# quadcopter.net
KiCad netlist of a schematic drawn in EAGLE
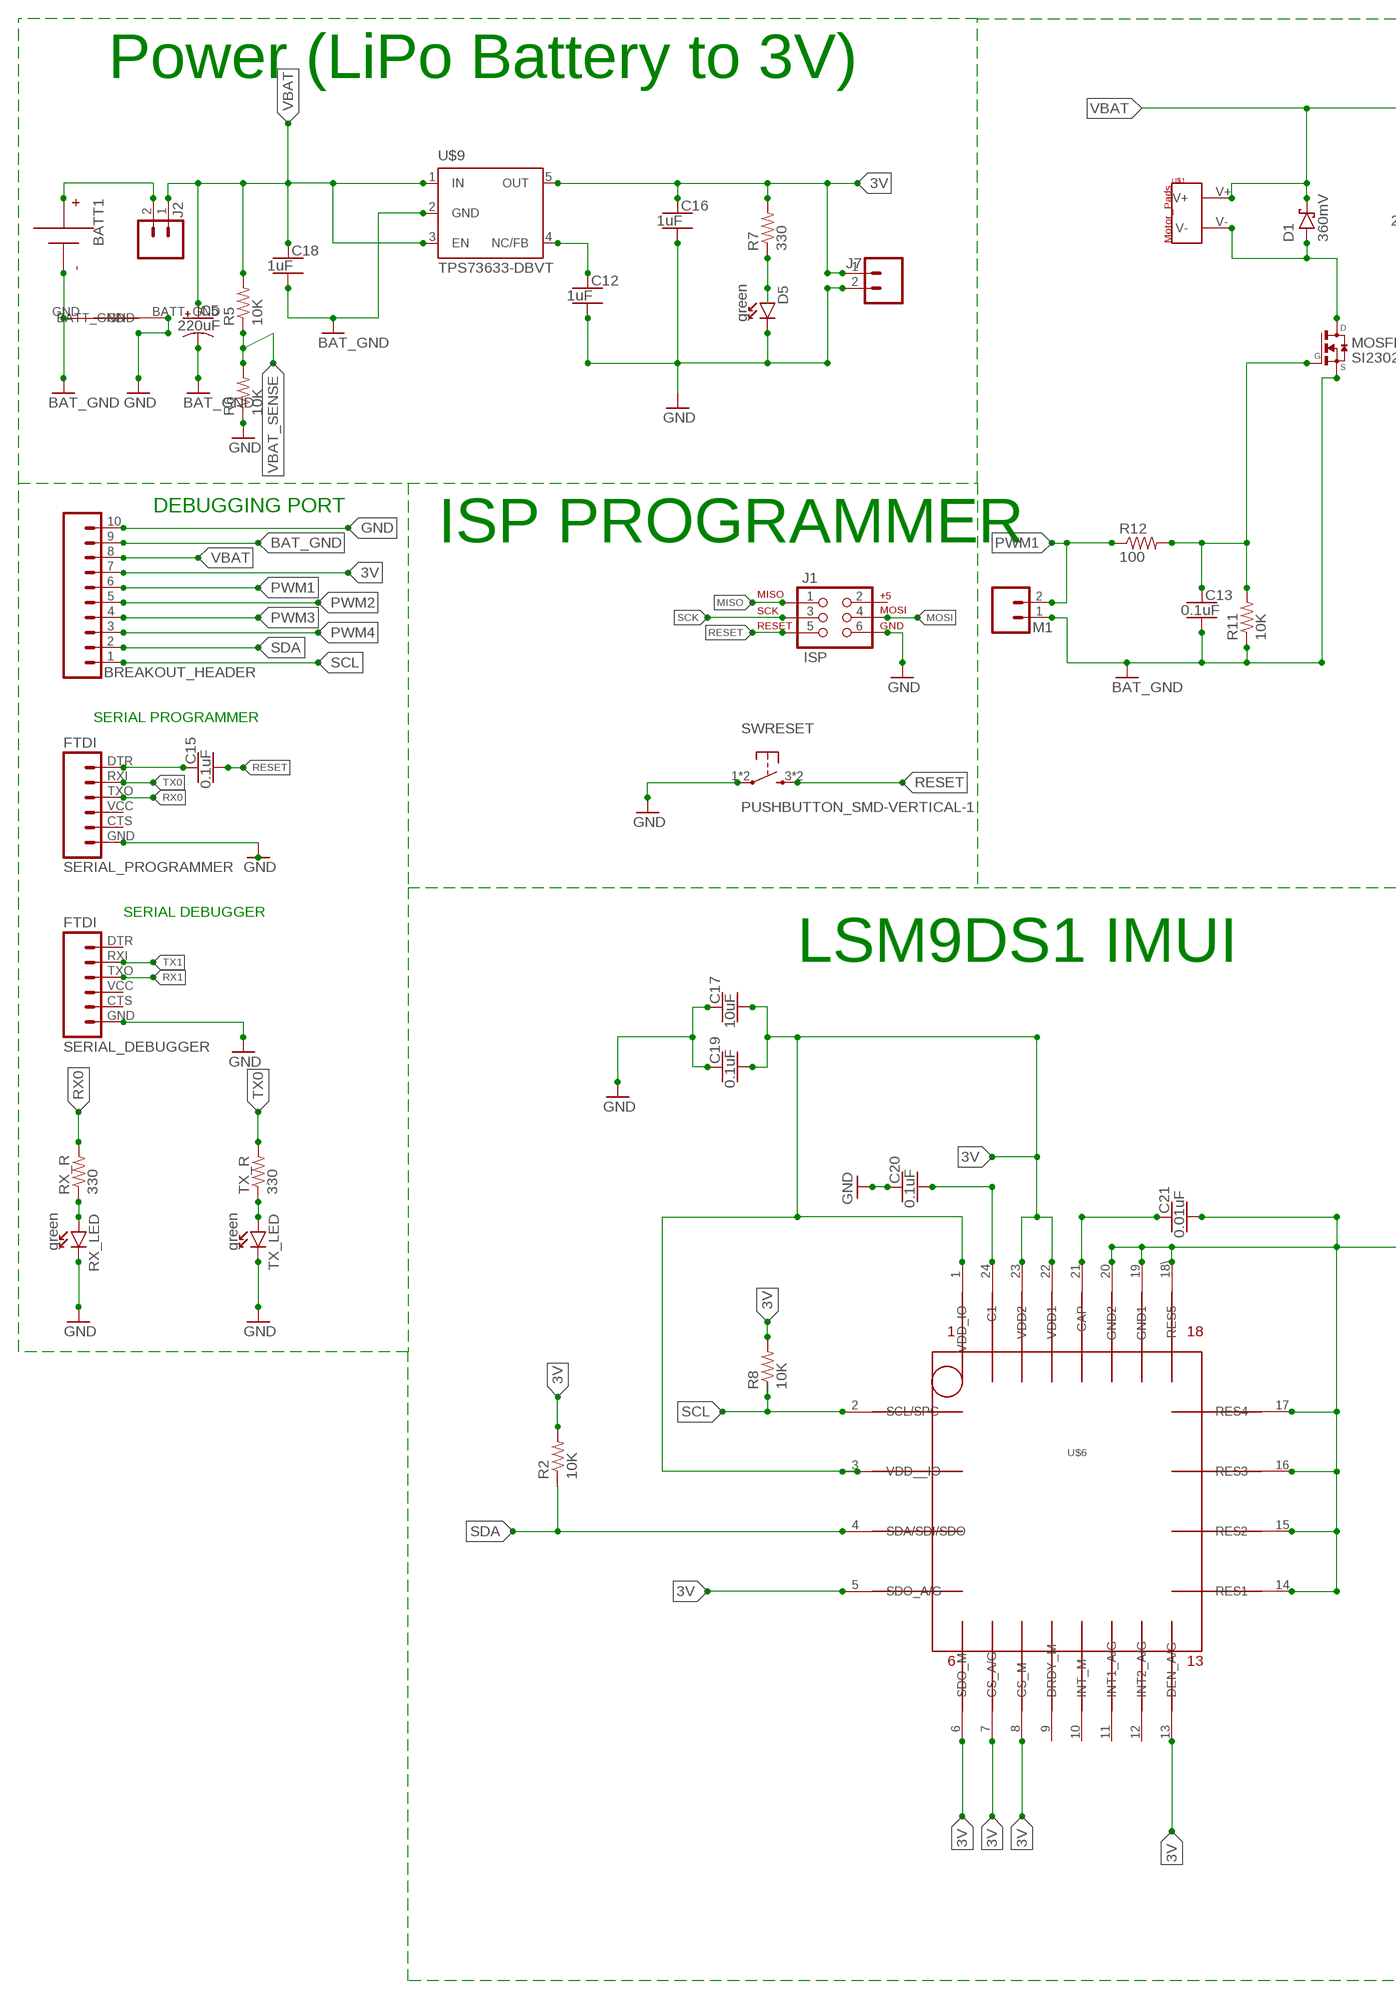
[diagram p0: schematic, sheet 1, part 1 of 2]
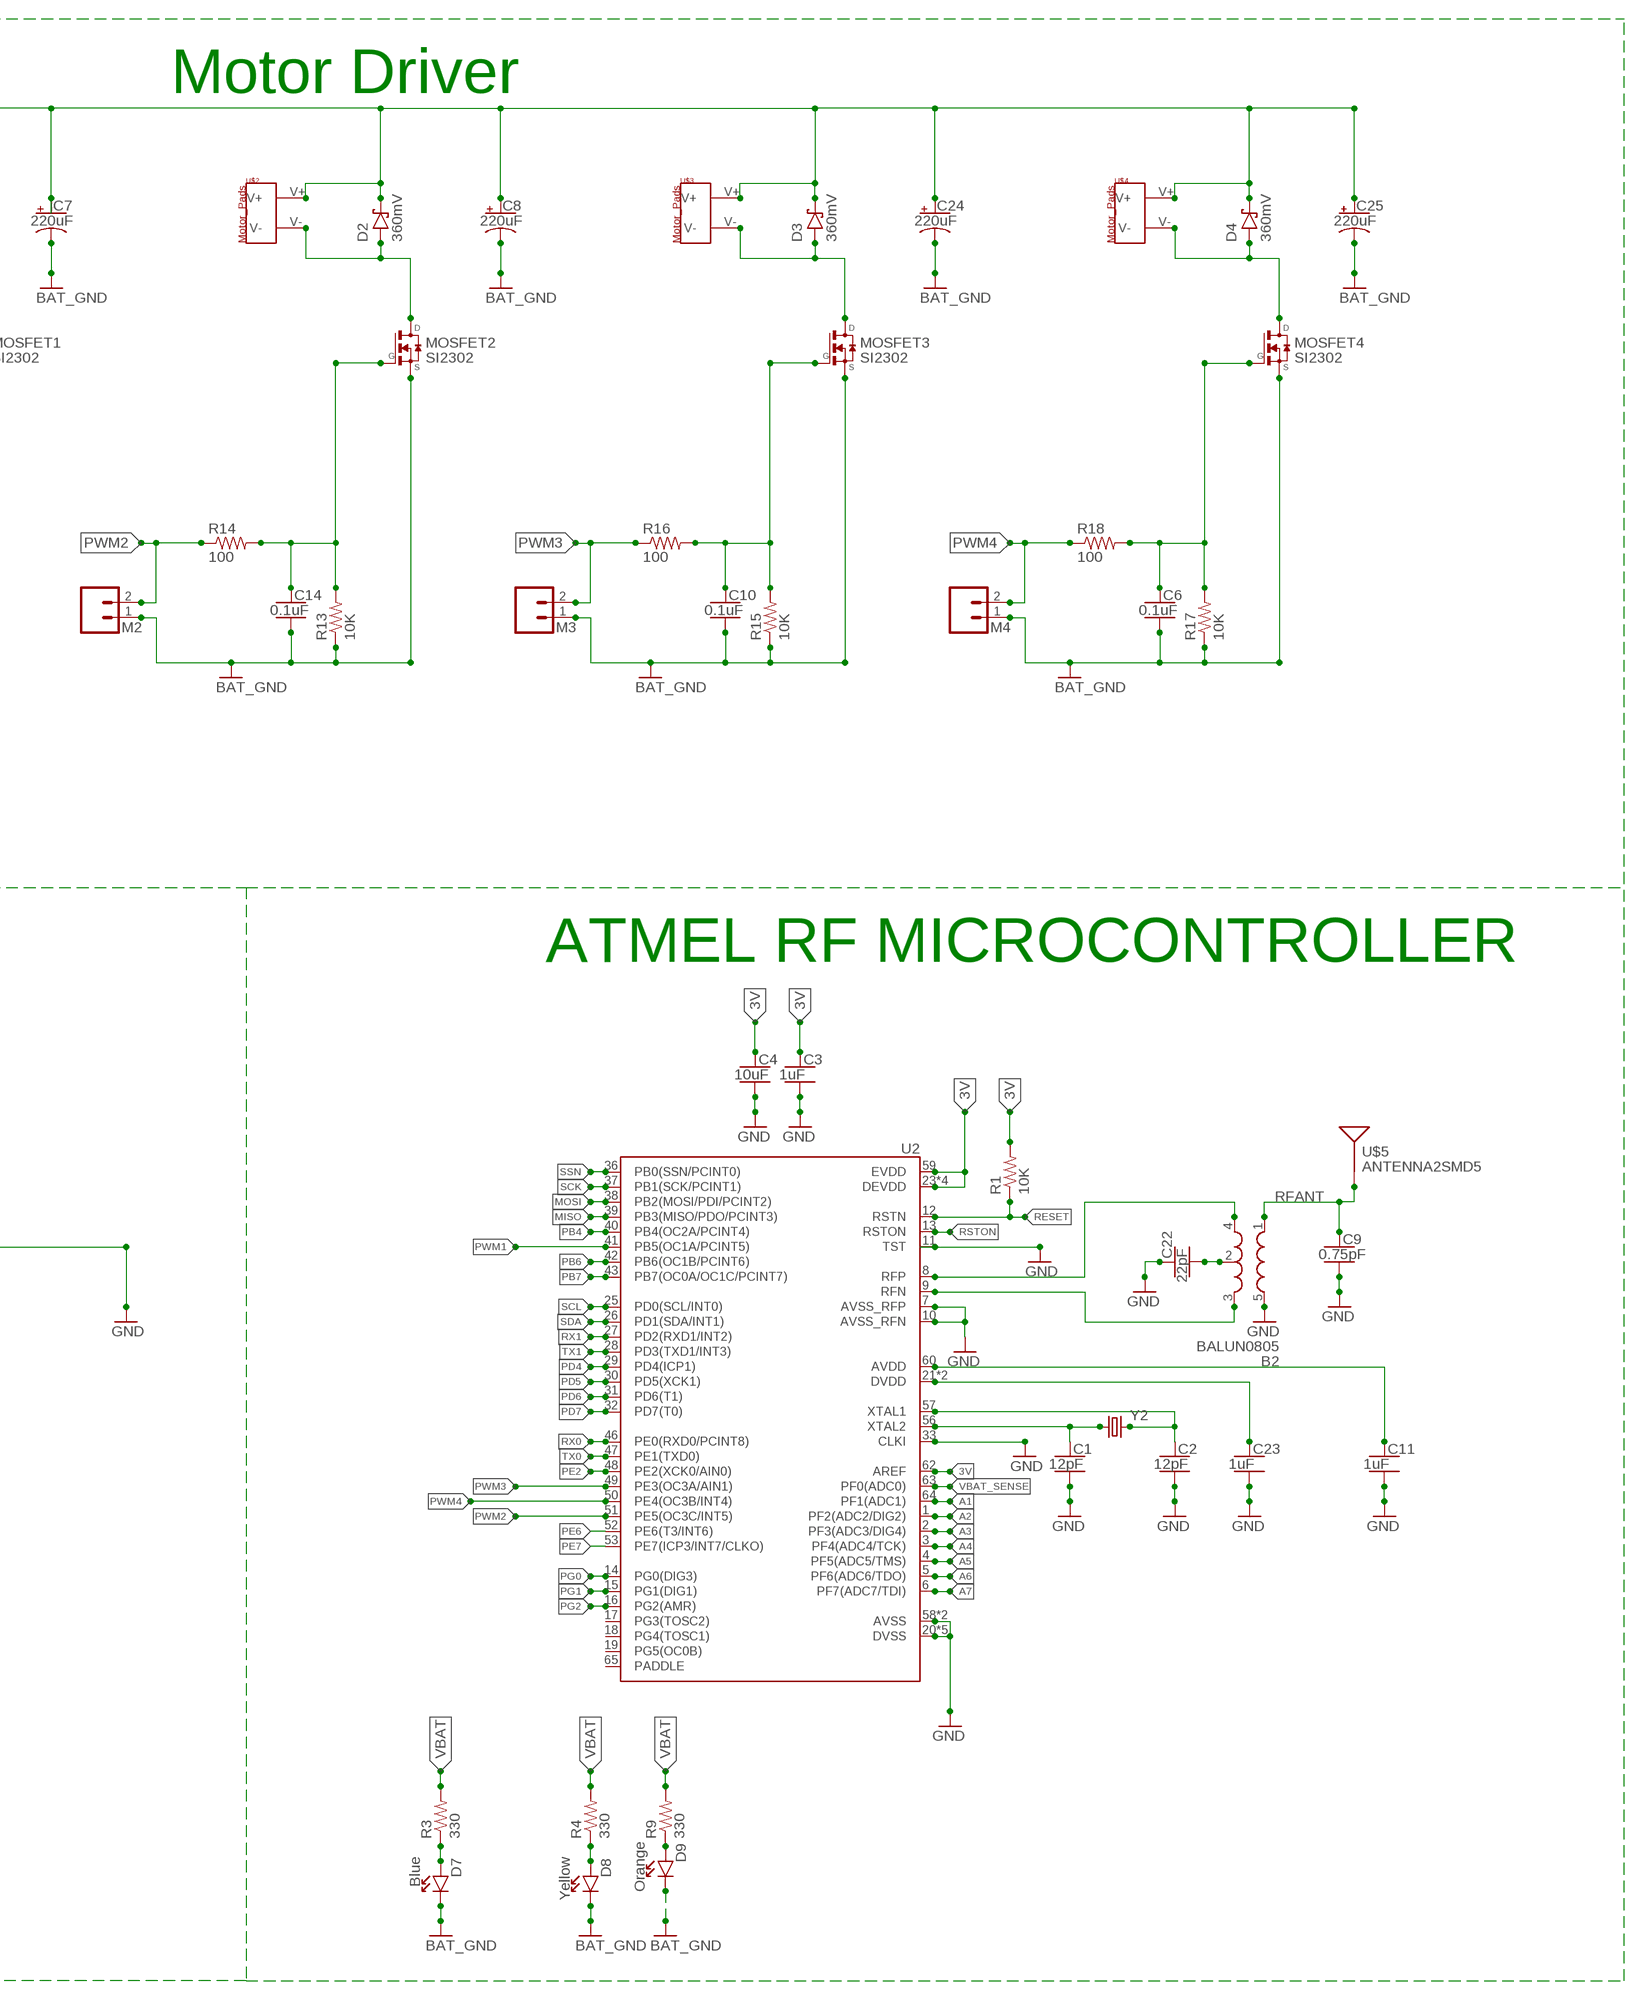
[diagram p1: schematic, sheet 1, part 2 of 2]

(export (version "E")
  (design (tool "Eeschema 10.0.6"))
  (components
    (comp (ref "B2")
      (value "BALUN0805")
      (footprint "eagle-import:BALUN")
      (fields (field (name "MFR") "Wurth Electronics Inc") (field (name "MPN") "748421245"))
      (libsource (lib "eagle-import") (part "BALUN0805"))
    )
    (comp (ref "BATT1")
      (value "BATTERY-HUBSAN-W/HOLDER")
      (footprint "eagle-import:BATTERY-W_HOLDER-380MAH-HUBSAN")
      (fields
        (field (name "MFR") "HUBSAN")
        (field (name "MPN") "X4-H107C-8-in-1")
        (field (name "CREATOR") "Swanson")
      )
      (libsource (lib "eagle-import") (part "BATTERY-HUBSAN-W/HOLDER"))
    )
    (comp (ref "BREAKOUT_HEADER")
      (value "SIP-10_TH-254X10")
      (footprint "eagle-import:HDRV10W63P254_10X1_2540X254H838_HS")
      (fields (field (name "MFR") "Amphenol FCI") (field (name "MPN") "68000-110HLF"))
      (libsource (lib "eagle-import") (part "SIP-10_TH-254X10"))
    )
    (comp (ref "C1")
      (value "12pF")
      (footprint "eagle-import:CAPC2012X140_HS")
      (fields
        (field (name "MFR") "Murata Electronics North America")
        (field (name "MPN") "GRM21A5C2E120JW01D")
      )
      (libsource (lib "eagle-import") (part "CAPACITOR-NP_SMD-2012-0805_CERAMIC-12PF"))
    )
    (comp (ref "C2")
      (value "12pF")
      (footprint "eagle-import:CAPC2012X140_HS")
      (fields
        (field (name "MFR") "Murata Electronics North America")
        (field (name "MPN") "GRM21A5C2E120JW01D")
      )
      (libsource (lib "eagle-import") (part "CAPACITOR-NP_SMD-2012-0805_CERAMIC-12PF"))
    )
    (comp (ref "C3")
      (value "1uF")
      (footprint "eagle-import:CAPC2012X140_HS")
      (fields
        (field (name "MFR") "Murata Electronics North America")
        (field (name "MPN") "GRM21BR71H105KA12L")
      )
      (libsource (lib "eagle-import") (part "CAPACITOR-NP_SMD-2012-0805_CERAMIC-1UF"))
    )
    (comp (ref "C4")
      (value "10uF")
      (footprint "eagle-import:CAPC2012X140_HS")
      (fields
        (field (name "MFR") "Murata Electronics North America")
        (field (name "MPN") "GRM21BR61E106KA73L")
      )
      (libsource (lib "eagle-import") (part "CAPACITOR-NP_SMD-2012-0805_CERAMIC-10UF"))
    )
    (comp (ref "C5")
      (value "220uF")
      (footprint "eagle-import:CAPMP7343X310_HS")
      (fields (field (name "MFR") "AVX Corporation") (field (name "MPN") "TAJD227K006RNJ"))
      (libsource (lib "eagle-import") (part "CAPACITOR-POL_SMD-7043-D_TANTALUM-220UF"))
    )
    (comp (ref "C6")
      (value "0.1uF")
      (footprint "eagle-import:CAPC2012X140_HS")
      (fields
        (field (name "MFR") "Murata Electronics North America")
        (field (name "MPN") "GRM21BR71H104KA01L")
      )
      (libsource (lib "eagle-import") (part "CAPACITOR-NP_SMD-2012-0805_CERAMIC-0.1UF"))
    )
    (comp (ref "C7")
      (value "220uF")
      (footprint "eagle-import:CAPMP7343X310_HS")
      (fields (field (name "MFR") "AVX Corporation") (field (name "MPN") "TAJD227K006RNJ"))
      (libsource (lib "eagle-import") (part "CAPACITOR-POL_SMD-7043-D_TANTALUM-220UF"))
    )
    (comp (ref "C8")
      (value "220uF")
      (footprint "eagle-import:CAPMP7343X310_HS")
      (fields (field (name "MFR") "AVX Corporation") (field (name "MPN") "TAJD227K006RNJ"))
      (libsource (lib "eagle-import") (part "CAPACITOR-POL_SMD-7043-D_TANTALUM-220UF"))
    )
    (comp (ref "C9")
      (value "0.75pF")
      (footprint "eagle-import:CAPC2012X140_HS")
      (fields
        (field (name "MFR") "Murata Electronics North America")
        (field (name "MPN") "GQM2195C2AR75CB01D")
      )
      (libsource (lib "eagle-import") (part "CAPACITOR-NP_SMD-2012-0805_CERAMIC-0.75PF"))
    )
    (comp (ref "C10")
      (value "0.1uF")
      (footprint "eagle-import:CAPC2012X140_HS")
      (fields
        (field (name "MFR") "Murata Electronics North America")
        (field (name "MPN") "GRM21BR71H104KA01L")
      )
      (libsource (lib "eagle-import") (part "CAPACITOR-NP_SMD-2012-0805_CERAMIC-0.1UF"))
    )
    (comp (ref "C11")
      (value "1uF")
      (footprint "eagle-import:CAPC2012X140_HS")
      (fields
        (field (name "MFR") "Murata Electronics North America")
        (field (name "MPN") "GRM21BR71H105KA12L")
      )
      (libsource (lib "eagle-import") (part "CAPACITOR-NP_SMD-2012-0805_CERAMIC-1UF"))
    )
    (comp (ref "C12")
      (value "1uF")
      (footprint "eagle-import:CAPC2012X140_HS")
      (fields
        (field (name "MFR") "Murata Electronics North America")
        (field (name "MPN") "GRM21BR71H105KA12L")
      )
      (libsource (lib "eagle-import") (part "CAPACITOR-NP_SMD-2012-0805_CERAMIC-1UF"))
    )
    (comp (ref "C13")
      (value "0.1uF")
      (footprint "eagle-import:CAPC2012X140_HS")
      (fields
        (field (name "MFR") "Murata Electronics North America")
        (field (name "MPN") "GRM21BR71H104KA01L")
      )
      (libsource (lib "eagle-import") (part "CAPACITOR-NP_SMD-2012-0805_CERAMIC-0.1UF"))
    )
    (comp (ref "C14")
      (value "0.1uF")
      (footprint "eagle-import:CAPC2012X140_HS")
      (fields
        (field (name "MFR") "Murata Electronics North America")
        (field (name "MPN") "GRM21BR71H104KA01L")
      )
      (libsource (lib "eagle-import") (part "CAPACITOR-NP_SMD-2012-0805_CERAMIC-0.1UF"))
    )
    (comp (ref "C15")
      (value "0.1uF")
      (footprint "eagle-import:CAPC2012X140_HS")
      (fields
        (field (name "MFR") "Murata Electronics North America")
        (field (name "MPN") "GRM21BR71H104KA01L")
      )
      (libsource (lib "eagle-import") (part "CAPACITOR-NP_SMD-2012-0805_CERAMIC-0.1UF"))
    )
    (comp (ref "C16")
      (value "1uF")
      (footprint "eagle-import:CAPC2012X140_HS")
      (fields
        (field (name "MFR") "Murata Electronics North America")
        (field (name "MPN") "GRM21BR71H105KA12L")
      )
      (libsource (lib "eagle-import") (part "CAPACITOR-NP_SMD-2012-0805_CERAMIC-1UF"))
    )
    (comp (ref "C17")
      (value "10uF")
      (footprint "eagle-import:CAPC2012X140_HS")
      (fields
        (field (name "MFR") "Murata Electronics North America")
        (field (name "MPN") "GRM21BR61E106KA73L")
      )
      (libsource (lib "eagle-import") (part "CAPACITOR-NP_SMD-2012-0805_CERAMIC-10UF"))
    )
    (comp (ref "C18")
      (value "1uF")
      (footprint "eagle-import:CAPC2012X140_HS")
      (fields
        (field (name "MFR") "Murata Electronics North America")
        (field (name "MPN") "GRM21BR71H105KA12L")
      )
      (libsource (lib "eagle-import") (part "CAPACITOR-NP_SMD-2012-0805_CERAMIC-1UF"))
    )
    (comp (ref "C19")
      (value "0.1uF")
      (footprint "eagle-import:CAPC2012X140_HS")
      (fields
        (field (name "MFR") "Murata Electronics North America")
        (field (name "MPN") "GRM21BR71H104KA01L")
      )
      (libsource (lib "eagle-import") (part "CAPACITOR-NP_SMD-2012-0805_CERAMIC-0.1UF"))
    )
    (comp (ref "C20")
      (value "0.1uF")
      (footprint "eagle-import:CAPC2012X140_HS")
      (fields
        (field (name "MFR") "Murata Electronics North America")
        (field (name "MPN") "GRM21BR71H104KA01L")
      )
      (libsource (lib "eagle-import") (part "CAPACITOR-NP_SMD-2012-0805_CERAMIC-0.1UF"))
    )
    (comp (ref "C21")
      (value "0.01uF")
      (footprint "eagle-import:CAPC2012X140_HS")
      (fields
        (field (name "MFR") "Murata Electronics North America")
        (field (name "MPN") "GRM2195C1H103FA01D")
      )
      (libsource (lib "eagle-import") (part "CAPACITOR-NP_SMD-2012-0805_CERAMIC-0.01UF"))
    )
    (comp (ref "C22")
      (value "22pF")
      (footprint "eagle-import:CAPC2012X140_HS")
      (fields
        (field (name "MFR") "Murata Electronics North America")
        (field (name "MPN") "GRM21A5C2E220JW01D")
      )
      (libsource (lib "eagle-import") (part "CAPACITOR-NP_SMD-2012-0805_CERAMIC-22PF"))
    )
    (comp (ref "C23")
      (value "1uF")
      (footprint "eagle-import:CAPC2012X140_HS")
      (fields
        (field (name "MFR") "Murata Electronics North America")
        (field (name "MPN") "GRM21BR71H105KA12L")
      )
      (libsource (lib "eagle-import") (part "CAPACITOR-NP_SMD-2012-0805_CERAMIC-1UF"))
    )
    (comp (ref "C24")
      (value "220uF")
      (footprint "eagle-import:CAPMP7343X310_HS")
      (fields (field (name "MFR") "AVX Corporation") (field (name "MPN") "TAJD227K006RNJ"))
      (libsource (lib "eagle-import") (part "CAPACITOR-POL_SMD-7043-D_TANTALUM-220UF"))
    )
    (comp (ref "C25")
      (value "220uF")
      (footprint "eagle-import:CAPMP7343X310_HS")
      (fields (field (name "MFR") "AVX Corporation") (field (name "MPN") "TAJD227K006RNJ"))
      (libsource (lib "eagle-import") (part "CAPACITOR-POL_SMD-7043-D_TANTALUM-220UF"))
    )
    (comp (ref "D1")
      (value "360mV")
      (footprint "eagle-import:SOD3716X135_HS")
      (fields
        (field (name "MFR") "Toshiba Semiconductor and Storage")
        (field (name "MPN") "CRS08(TE85L,Q,M)")
      )
      (libsource (lib "eagle-import") (part "DIODE-SCHOTTKY_SMD-SOD123-360MV"))
    )
    (comp (ref "D2")
      (value "360mV")
      (footprint "eagle-import:SOD3716X135_HS")
      (fields
        (field (name "MFR") "Toshiba Semiconductor and Storage")
        (field (name "MPN") "CRS08(TE85L,Q,M)")
      )
      (libsource (lib "eagle-import") (part "DIODE-SCHOTTKY_SMD-SOD123-360MV"))
    )
    (comp (ref "D3")
      (value "360mV")
      (footprint "eagle-import:SOD3716X135_HS")
      (fields
        (field (name "MFR") "Toshiba Semiconductor and Storage")
        (field (name "MPN") "CRS08(TE85L,Q,M)")
      )
      (libsource (lib "eagle-import") (part "DIODE-SCHOTTKY_SMD-SOD123-360MV"))
    )
    (comp (ref "D4")
      (value "360mV")
      (footprint "eagle-import:SOD3716X135_HS")
      (fields
        (field (name "MFR") "Toshiba Semiconductor and Storage")
        (field (name "MPN") "CRS08(TE85L,Q,M)")
      )
      (libsource (lib "eagle-import") (part "DIODE-SCHOTTKY_SMD-SOD123-360MV"))
    )
    (comp (ref "D5")
      (value "green")
      (footprint "eagle-import:LEDSC125X200X120-2_HS")
      (fields (field (name "MFR") "Lite-On Inc") (field (name "MPN") "LTST-C170GKT"))
      (libsource (lib "eagle-import") (part "DIODE-LED_SMD-2012-0805-GREEN"))
    )
    (comp (ref "D7")
      (value "Blue")
      (footprint "eagle-import:LEDSC125X200X120-2_HS")
      (libsource (lib "eagle-import") (part "DIODE-LED_SMD-2012-0805"))
    )
    (comp (ref "D8")
      (value "Yellow")
      (footprint "eagle-import:LEDSC125X200X120-2_HS")
      (libsource (lib "eagle-import") (part "DIODE-LED_SMD-2012-0805"))
    )
    (comp (ref "D9")
      (value "Orange")
      (footprint "eagle-import:LEDSC125X200X120-2_HS")
      (libsource (lib "eagle-import") (part "DIODE-LED_SMD-2012-0805"))
    )
    (comp (ref "J1")
      (value "ISP")
      (footprint "eagle-import:2X3-NS")
      (libsource (lib "eagle-import") (part "AVR_SPI_PRG_6NS"))
    )
    (comp (ref "J2")
      (value "MALE_HEADER_2POS-2X1-0.1IN")
      (footprint "eagle-import:MALE_HEADER_2X1_0.1IN")
      (fields
        (field (name "MFR") "3M")
        (field (name "MPN") "961102-6404-AR")
        (field (name "CREATOR") "SWANSON")
      )
      (libsource (lib "eagle-import") (part "MALE_HEADER_2POS-2X1-0.1IN"))
    )
    (comp (ref "J7")
      (value "MALE_HEADER_2POS-2X1-0.1IN")
      (footprint "eagle-import:MALE_HEADER_2X1_0.1IN")
      (fields
        (field (name "MFR") "3M")
        (field (name "MPN") "961102-6404-AR")
        (field (name "CREATOR") "SWANSON")
      )
      (libsource (lib "eagle-import") (part "MALE_HEADER_2POS-2X1-0.1IN"))
    )
    (comp (ref "M1")
      (value "MALE_HEADER_2POS-2X1-0.1IN")
      (footprint "eagle-import:MALE_HEADER_2X1_0.1IN")
      (fields
        (field (name "MFR") "3M")
        (field (name "MPN") "961102-6404-AR")
        (field (name "CREATOR") "SWANSON")
      )
      (libsource (lib "eagle-import") (part "MALE_HEADER_2POS-2X1-0.1IN"))
    )
    (comp (ref "M2")
      (value "MALE_HEADER_2POS-2X1-0.1IN")
      (footprint "eagle-import:MALE_HEADER_2X1_0.1IN")
      (fields
        (field (name "MFR") "3M")
        (field (name "MPN") "961102-6404-AR")
        (field (name "CREATOR") "SWANSON")
      )
      (libsource (lib "eagle-import") (part "MALE_HEADER_2POS-2X1-0.1IN"))
    )
    (comp (ref "M3")
      (value "MALE_HEADER_2POS-2X1-0.1IN")
      (footprint "eagle-import:MALE_HEADER_2X1_0.1IN")
      (fields
        (field (name "MFR") "3M")
        (field (name "MPN") "961102-6404-AR")
        (field (name "CREATOR") "SWANSON")
      )
      (libsource (lib "eagle-import") (part "MALE_HEADER_2POS-2X1-0.1IN"))
    )
    (comp (ref "M4")
      (value "MALE_HEADER_2POS-2X1-0.1IN")
      (footprint "eagle-import:MALE_HEADER_2X1_0.1IN")
      (fields
        (field (name "MFR") "3M")
        (field (name "MPN") "961102-6404-AR")
        (field (name "CREATOR") "SWANSON")
      )
      (libsource (lib "eagle-import") (part "MALE_HEADER_2POS-2X1-0.1IN"))
    )
    (comp (ref "MOSFET1")
      (value "SI2302")
      (footprint "eagle-import:SOT23")
      (fields (field (name "MF") "Vishay Siliconix") (field (name "MP") "SI2302CDS-T1-E3"))
      (libsource (lib "eagle-import") (part "SI2302"))
    )
    (comp (ref "MOSFET2")
      (value "SI2302")
      (footprint "eagle-import:SOT23")
      (fields (field (name "MF") "Vishay Siliconix") (field (name "MP") "SI2302CDS-T1-E3"))
      (libsource (lib "eagle-import") (part "SI2302"))
    )
    (comp (ref "MOSFET3")
      (value "SI2302")
      (footprint "eagle-import:SOT23")
      (fields (field (name "MF") "Vishay Siliconix") (field (name "MP") "SI2302CDS-T1-E3"))
      (libsource (lib "eagle-import") (part "SI2302"))
    )
    (comp (ref "MOSFET4")
      (value "SI2302")
      (footprint "eagle-import:SOT23")
      (fields (field (name "MF") "Vishay Siliconix") (field (name "MP") "SI2302CDS-T1-E3"))
      (libsource (lib "eagle-import") (part "SI2302"))
    )
    (comp (ref "R1")
      (value "10K")
      (footprint "eagle-import:RESC2012X60_HS")
      (fields (field (name "MFR") "Yageo") (field (name "MPN") "RC0805JR-0710KL"))
      (libsource (lib "eagle-import") (part "RESISTOR_SMD-2012-0805-10K"))
    )
    (comp (ref "R2")
      (value "10K")
      (footprint "eagle-import:RESC2012X60_HS")
      (fields (field (name "MFR") "Yageo") (field (name "MPN") "RC0805JR-0710KL"))
      (libsource (lib "eagle-import") (part "RESISTOR_SMD-2012-0805-10K"))
    )
    (comp (ref "R3")
      (value "330")
      (footprint "eagle-import:RESC2012X60_HS")
      (fields (field (name "MFR") "Yageo") (field (name "MPN") "RC0805JR-07330RL"))
      (libsource (lib "eagle-import") (part "RESISTOR_SMD-2012-0805-330"))
    )
    (comp (ref "R4")
      (value "330")
      (footprint "eagle-import:RESC2012X60_HS")
      (fields (field (name "MFR") "Yageo") (field (name "MPN") "RC0805JR-07330RL"))
      (libsource (lib "eagle-import") (part "RESISTOR_SMD-2012-0805-330"))
    )
    (comp (ref "R5")
      (value "10K")
      (footprint "eagle-import:RESC2012X60_HS")
      (fields (field (name "MFR") "Yageo") (field (name "MPN") "RC0805JR-0710KL"))
      (libsource (lib "eagle-import") (part "RESISTOR_SMD-2012-0805-10K"))
    )
    (comp (ref "R6")
      (value "10K")
      (footprint "eagle-import:RESC2012X60_HS")
      (fields (field (name "MFR") "Yageo") (field (name "MPN") "RC0805JR-0710KL"))
      (libsource (lib "eagle-import") (part "RESISTOR_SMD-2012-0805-10K"))
    )
    (comp (ref "R7")
      (value "330")
      (footprint "eagle-import:RESC2012X60_HS")
      (fields (field (name "MFR") "Yageo") (field (name "MPN") "RC0805JR-07330RL"))
      (libsource (lib "eagle-import") (part "RESISTOR_SMD-2012-0805-330"))
    )
    (comp (ref "R8")
      (value "10K")
      (footprint "eagle-import:RESC2012X60_HS")
      (fields (field (name "MFR") "Yageo") (field (name "MPN") "RC0805JR-0710KL"))
      (libsource (lib "eagle-import") (part "RESISTOR_SMD-2012-0805-10K"))
    )
    (comp (ref "R9")
      (value "330")
      (footprint "eagle-import:RESC2012X60_HS")
      (fields (field (name "MFR") "Yageo") (field (name "MPN") "RC0805JR-07330RL"))
      (libsource (lib "eagle-import") (part "RESISTOR_SMD-2012-0805-330"))
    )
    (comp (ref "R11")
      (value "10K")
      (footprint "eagle-import:RESC2012X60_HS")
      (fields (field (name "MFR") "Yageo") (field (name "MPN") "RC0805JR-0710KL"))
      (libsource (lib "eagle-import") (part "RESISTOR_SMD-2012-0805-10K"))
    )
    (comp (ref "R12")
      (value "100")
      (footprint "eagle-import:RESC2012X60_HS")
      (fields (field (name "MFR") "Yageo") (field (name "MPN") "RC0805JR-07100RL"))
      (libsource (lib "eagle-import") (part "RESISTOR_SMD-2012-0805-100"))
    )
    (comp (ref "R13")
      (value "10K")
      (footprint "eagle-import:RESC2012X60_HS")
      (fields (field (name "MFR") "Yageo") (field (name "MPN") "RC0805JR-0710KL"))
      (libsource (lib "eagle-import") (part "RESISTOR_SMD-2012-0805-10K"))
    )
    (comp (ref "R14")
      (value "100")
      (footprint "eagle-import:RESC2012X60_HS")
      (fields (field (name "MFR") "Yageo") (field (name "MPN") "RC0805JR-07100RL"))
      (libsource (lib "eagle-import") (part "RESISTOR_SMD-2012-0805-100"))
    )
    (comp (ref "R15")
      (value "10K")
      (footprint "eagle-import:RESC2012X60_HS")
      (fields (field (name "MFR") "Yageo") (field (name "MPN") "RC0805JR-0710KL"))
      (libsource (lib "eagle-import") (part "RESISTOR_SMD-2012-0805-10K"))
    )
    (comp (ref "R16")
      (value "100")
      (footprint "eagle-import:RESC2012X60_HS")
      (fields (field (name "MFR") "Yageo") (field (name "MPN") "RC0805JR-07100RL"))
      (libsource (lib "eagle-import") (part "RESISTOR_SMD-2012-0805-100"))
    )
    (comp (ref "R17")
      (value "10K")
      (footprint "eagle-import:RESC2012X60_HS")
      (fields (field (name "MFR") "Yageo") (field (name "MPN") "RC0805JR-0710KL"))
      (libsource (lib "eagle-import") (part "RESISTOR_SMD-2012-0805-10K"))
    )
    (comp (ref "R18")
      (value "100")
      (footprint "eagle-import:RESC2012X60_HS")
      (fields (field (name "MFR") "Yageo") (field (name "MPN") "RC0805JR-07100RL"))
      (libsource (lib "eagle-import") (part "RESISTOR_SMD-2012-0805-100"))
    )
    (comp (ref "RX_LED")
      (value "green")
      (footprint "eagle-import:LEDSC125X200X120-2_HS")
      (fields (field (name "MFR") "Lite-On Inc") (field (name "MPN") "LTST-C170GKT"))
      (libsource (lib "eagle-import") (part "DIODE-LED_SMD-2012-0805-GREEN"))
    )
    (comp (ref "RX_R")
      (value "330")
      (footprint "eagle-import:RESC2012X60_HS")
      (fields (field (name "MFR") "Yageo") (field (name "MPN") "RC0805JR-07330RL"))
      (libsource (lib "eagle-import") (part "RESISTOR_SMD-2012-0805-330"))
    )
    (comp (ref "SERIAL_DEBUGGER")
      (value "FTDI")
      (footprint "eagle-import:FTDI_BASIC")
      (libsource (lib "eagle-import") (part "FTDI_BASICPTH"))
    )
    (comp (ref "SERIAL_PROGRAMMER")
      (value "FTDI")
      (footprint "eagle-import:FTDI_BASIC")
      (libsource (lib "eagle-import") (part "FTDI_BASICPTH"))
    )
    (comp (ref "SWRESET")
      (value "PUSHBUTTON_SMD-VERTICAL-1")
      (footprint "eagle-import:TE_FSM8JSMA_HS")
      (fields (field (name "MFR") "TE Connectivity Alcoswitch Switches") (field (name "MPN") "FSM4JSMA"))
      (libsource (lib "eagle-import") (part "PUSHBUTTON_SMD-VERTICAL-1"))
    )
    (comp (ref "TX_LED")
      (value "green")
      (footprint "eagle-import:LEDSC125X200X120-2_HS")
      (fields (field (name "MFR") "Lite-On Inc") (field (name "MPN") "LTST-C170GKT"))
      (libsource (lib "eagle-import") (part "DIODE-LED_SMD-2012-0805-GREEN"))
    )
    (comp (ref "TX_R")
      (value "330")
      (footprint "eagle-import:RESC2012X60_HS")
      (fields (field (name "MFR") "Yageo") (field (name "MPN") "RC0805JR-07330RL"))
      (libsource (lib "eagle-import") (part "RESISTOR_SMD-2012-0805-330"))
    )
    (comp (ref "U$1")
      (value "MOTOR_PADS")
      (footprint "eagle-import:MOTOR_PADS")
      (fields (field (name "MFR") "NA"))
      (libsource (lib "eagle-import") (part "MOTOR_PADS"))
    )
    (comp (ref "U$2")
      (value "MOTOR_PADS")
      (footprint "eagle-import:MOTOR_PADS")
      (fields (field (name "MFR") "NA"))
      (libsource (lib "eagle-import") (part "MOTOR_PADS"))
    )
    (comp (ref "U$3")
      (value "MOTOR_PADS")
      (footprint "eagle-import:MOTOR_PADS")
      (fields (field (name "MFR") "NA"))
      (libsource (lib "eagle-import") (part "MOTOR_PADS"))
    )
    (comp (ref "U$4")
      (value "MOTOR_PADS")
      (footprint "eagle-import:MOTOR_PADS")
      (fields (field (name "MFR") "NA"))
      (libsource (lib "eagle-import") (part "MOTOR_PADS"))
    )
    (comp (ref "U$5")
      (value "ANTENNA2SMD5")
      (footprint "eagle-import:ANTENNA-CHIP5")
      (fields (field (name "MFR") "Linx Technologies Inc.") (field (name "MPN") "ANT-2.45-CHP-T"))
      (libsource (lib "eagle-import") (part "ANTENNA2SMD5"))
    )
    (comp (ref "U$6")
      (value "IMULAST")
      (footprint "eagle-import:LGA-24_4MM")
      (libsource (lib "eagle-import") (part "IMULAST"))
    )
    (comp (ref "U$7")
      (value "WIRE_BRIDGE")
      (footprint "eagle-import:WIRE_BRIGE")
      (libsource (lib "eagle-import") (part "WIRE_BRIDGE"))
    )
    (comp (ref "U$9")
      (value "TPS73633-DBVT")
      (footprint "eagle-import:SOT23-DBV")
      (fields (field (name "MFR") "Texas Instruments") (field (name "MPN") "LP3985IM5X-3.0/NOPB"))
      (libsource (lib "eagle-import") (part "TPS73633-DBVT"))
    )
    (comp (ref "U2")
      (value "ATMEGA128RFA1")
      (footprint "eagle-import:QFN-64")
      (fields
        (field (name "MFR") "Atmel")
        (field (name "MPN") "ATMEGA128RFA1-ZUR00")
        (field (name "CREATOR") "Swanson")
      )
      (libsource (lib "eagle-import") (part "ATMEGA128RFA1"))
    )
    (comp (ref "Y2")
      (value "CRYSTAL5X3")
      (footprint "eagle-import:CRYSTAL-SMD-5X3")
      (fields (field (name "MFR") "Abracon LLC") (field (name "MPN") "ABM3B-16.000MHZ-B2-T"))
      (libsource (lib "eagle-import") (part "CRYSTAL5X3"))
    )
  )
  (nets
    (net (code "1") (name "/RFANT") (class "Default")
      (node (ref "B2") (pin "1") (pinfunction "IN_1") (pintype "bidirectional"))
      (node (ref "C9") (pin "1") (pinfunction "1_1") (pintype "passive"))
      (node (ref "U$5") (pin "FEED") (pinfunction "SIGNAL_FEED") (pintype "bidirectional"))
    )
    (net (code "2") (name "3V") (class "Default")
      (node (ref "BREAKOUT_HEADER") (pin "7") (pinfunction "7_7") (pintype "passive"))
      (node (ref "C16") (pin "1") (pinfunction "1_1") (pintype "passive"))
      (node (ref "C17") (pin "2") (pinfunction "2_2") (pintype "passive"))
      (node (ref "C19") (pin "2") (pinfunction "2_2") (pintype "passive"))
      (node (ref "C3") (pin "1") (pinfunction "1_1") (pintype "passive"))
      (node (ref "C4") (pin "1") (pinfunction "1_1") (pintype "passive"))
      (node (ref "J7") (pin "1") (pinfunction "1_1") (pintype "passive"))
      (node (ref "R1") (pin "2") (pinfunction "2_2") (pintype "passive"))
      (node (ref "R2") (pin "2") (pinfunction "2_2") (pintype "passive"))
      (node (ref "R7") (pin "2") (pinfunction "2_2") (pintype "passive"))
      (node (ref "R8") (pin "2") (pinfunction "2_2") (pintype "passive"))
      (node (ref "U$6") (pin "1") (pinfunction "VDD_IO_1") (pintype "bidirectional"))
      (node (ref "U$6") (pin "13") (pinfunction "DEN_A/G_13") (pintype "bidirectional"))
      (node (ref "U$6") (pin "22") (pinfunction "VDD1_22") (pintype "bidirectional"))
      (node (ref "U$6") (pin "23") (pinfunction "VDD2_23") (pintype "bidirectional"))
      (node (ref "U$6") (pin "3") (pinfunction "VDD__IO_3") (pintype "bidirectional"))
      (node (ref "U$6") (pin "5") (pinfunction "SDO_A/G_5") (pintype "bidirectional"))
      (node (ref "U$6") (pin "6") (pinfunction "SDO_M_6") (pintype "bidirectional"))
      (node (ref "U$6") (pin "7") (pinfunction "CS_A/G_7") (pintype "bidirectional"))
      (node (ref "U$6") (pin "8") (pinfunction "CS_M_8") (pintype "bidirectional"))
      (node (ref "U$9") (pin "5") (pinfunction "OUT_5") (pintype "passive"))
      (node (ref "U2") (pin "23") (pinfunction "DEVDD_23") (pintype "bidirectional"))
      (node (ref "U2") (pin "34") (pinfunction "DEVDD_34") (pintype "bidirectional"))
      (node (ref "U2") (pin "44") (pinfunction "DEVDD_44") (pintype "bidirectional"))
      (node (ref "U2") (pin "54") (pinfunction "DEVDD_54") (pintype "bidirectional"))
      (node (ref "U2") (pin "59") (pinfunction "EVDD_59") (pintype "bidirectional"))
      (node (ref "U2") (pin "62") (pinfunction "AREF_62") (pintype "bidirectional"))
    )
    (net (code "3") (name "A1") (class "Default")
      (node (ref "U2") (pin "64") (pinfunction "PF1(ADC1)_64") (pintype "bidirectional"))
    )
    (net (code "4") (name "A2") (class "Default")
      (node (ref "U2") (pin "1") (pinfunction "PF2(ADC2/DIG2)_1") (pintype "bidirectional"))
    )
    (net (code "5") (name "A3") (class "Default")
      (node (ref "U2") (pin "2") (pinfunction "PF3(ADC3/DIG4)_2") (pintype "bidirectional"))
    )
    (net (code "6") (name "A4") (class "Default")
      (node (ref "U2") (pin "3") (pinfunction "PF4(ADC4/TCK)_3") (pintype "bidirectional"))
    )
    (net (code "7") (name "A5") (class "Default")
      (node (ref "U2") (pin "4") (pinfunction "PF5(ADC5/TMS)_4") (pintype "bidirectional"))
    )
    (net (code "8") (name "A6") (class "Default")
      (node (ref "U2") (pin "5") (pinfunction "PF6(ADC6/TDO)_5") (pintype "bidirectional"))
    )
    (net (code "9") (name "A7") (class "Default")
      (node (ref "U2") (pin "6") (pinfunction "PF7(ADC7/TDI)_6") (pintype "bidirectional"))
    )
    (net (code "10") (name "BAT_GND") (class "Default")
      (node (ref "BATT1") (pin "-") (pinfunction "N_-") (pintype "bidirectional"))
      (node (ref "BREAKOUT_HEADER") (pin "9") (pinfunction "9_9") (pintype "passive"))
      (node (ref "C10") (pin "2") (pinfunction "2_2") (pintype "passive"))
      (node (ref "C13") (pin "2") (pinfunction "2_2") (pintype "passive"))
      (node (ref "C14") (pin "2") (pinfunction "2_2") (pintype "passive"))
      (node (ref "C18") (pin "2") (pinfunction "2_2") (pintype "passive"))
      (node (ref "C24") (pin "2") (pinfunction "-_2") (pintype "passive"))
      (node (ref "C25") (pin "2") (pinfunction "-_2") (pintype "passive"))
      (node (ref "C5") (pin "2") (pinfunction "-_2") (pintype "passive"))
      (node (ref "C6") (pin "2") (pinfunction "2_2") (pintype "passive"))
      (node (ref "C7") (pin "2") (pinfunction "-_2") (pintype "passive"))
      (node (ref "C8") (pin "2") (pinfunction "-_2") (pintype "passive"))
      (node (ref "D7") (pin "C") (pinfunction "C_C") (pintype "passive"))
      (node (ref "D8") (pin "C") (pinfunction "C_C") (pintype "passive"))
      (node (ref "D9") (pin "C") (pinfunction "C_C") (pintype "passive"))
      (node (ref "M1") (pin "1") (pinfunction "1_1") (pintype "passive"))
      (node (ref "M2") (pin "1") (pinfunction "1_1") (pintype "passive"))
      (node (ref "M3") (pin "1") (pinfunction "1_1") (pintype "passive"))
      (node (ref "M4") (pin "1") (pinfunction "1_1") (pintype "passive"))
      (node (ref "MOSFET1") (pin "2") (pinfunction "S_2") (pintype "passive"))
      (node (ref "MOSFET2") (pin "2") (pinfunction "S_2") (pintype "passive"))
      (node (ref "MOSFET3") (pin "2") (pinfunction "S_2") (pintype "passive"))
      (node (ref "MOSFET4") (pin "2") (pinfunction "S_2") (pintype "passive"))
      (node (ref "R11") (pin "1") (pinfunction "1_1") (pintype "passive"))
      (node (ref "R13") (pin "1") (pinfunction "1_1") (pintype "passive"))
      (node (ref "R15") (pin "1") (pinfunction "1_1") (pintype "passive"))
      (node (ref "R17") (pin "1") (pinfunction "1_1") (pintype "passive"))
      (node (ref "U$7") (pin "GND") (pinfunction "GND_GND") (pintype "bidirectional"))
      (node (ref "U$9") (pin "2") (pinfunction "GND_2") (pintype "input"))
    )
    (net (code "11") (name "GND") (class "Default")
      (node (ref "B2") (pin "5") (pinfunction "GND_5") (pintype "bidirectional"))
      (node (ref "BREAKOUT_HEADER") (pin "10") (pinfunction "10_10") (pintype "passive"))
      (node (ref "C1") (pin "2") (pinfunction "2_2") (pintype "passive"))
      (node (ref "C11") (pin "2") (pinfunction "2_2") (pintype "passive"))
      (node (ref "C12") (pin "2") (pinfunction "2_2") (pintype "passive"))
      (node (ref "C16") (pin "2") (pinfunction "2_2") (pintype "passive"))
      (node (ref "C17") (pin "1") (pinfunction "1_1") (pintype "passive"))
      (node (ref "C19") (pin "1") (pinfunction "1_1") (pintype "passive"))
      (node (ref "C2") (pin "2") (pinfunction "2_2") (pintype "passive"))
      (node (ref "C20") (pin "1") (pinfunction "1_1") (pintype "passive"))
      (node (ref "C21") (pin "2") (pinfunction "2_2") (pintype "passive"))
      (node (ref "C22") (pin "1") (pinfunction "1_1") (pintype "passive"))
      (node (ref "C23") (pin "2") (pinfunction "2_2") (pintype "passive"))
      (node (ref "C3") (pin "2") (pinfunction "2_2") (pintype "passive"))
      (node (ref "C4") (pin "2") (pinfunction "2_2") (pintype "passive"))
      (node (ref "C9") (pin "2") (pinfunction "2_2") (pintype "passive"))
      (node (ref "D5") (pin "C") (pinfunction "C_C") (pintype "passive"))
      (node (ref "J1") (pin "6") (pinfunction "6_6") (pintype "passive"))
      (node (ref "J7") (pin "2") (pinfunction "2_2") (pintype "passive"))
      (node (ref "R6") (pin "1") (pinfunction "1_1") (pintype "passive"))
      (node (ref "RX_LED") (pin "C") (pinfunction "C_C") (pintype "passive"))
      (node (ref "SERIAL_DEBUGGER") (pin "GND") (pinfunction "6_GND") (pintype "passive"))
      (node (ref "SERIAL_PROGRAMMER") (pin "GND") (pinfunction "6_GND") (pintype "passive"))
      (node (ref "SWRESET") (pin "1") (pinfunction "1_1") (pintype "passive"))
      (node (ref "SWRESET") (pin "2") (pinfunction "1_2") (pintype "passive"))
      (node (ref "TX_LED") (pin "C") (pinfunction "C_C") (pintype "passive"))
      (node (ref "U$6") (pin "14") (pinfunction "RES1_14") (pintype "bidirectional"))
      (node (ref "U$6") (pin "15") (pinfunction "RES2_15") (pintype "bidirectional"))
      (node (ref "U$6") (pin "16") (pinfunction "RES3_16") (pintype "bidirectional"))
      (node (ref "U$6") (pin "17") (pinfunction "RES4_17") (pintype "bidirectional"))
      (node (ref "U$6") (pin "18\\") (pinfunction "RES5_18\\") (pintype "bidirectional"))
      (node (ref "U$6") (pin "19") (pinfunction "GND1_19") (pintype "bidirectional"))
      (node (ref "U$6") (pin "20") (pinfunction "GND2_20") (pintype "bidirectional"))
      (node (ref "U$7") (pin "BATT_GND") (pinfunction "BATT_GND_BATT_GND") (pintype "bidirectional"))
      (node (ref "U2") (pin "10") (pinfunction "AVSS_RFN_10") (pintype "bidirectional"))
      (node (ref "U2") (pin "11") (pinfunction "TST_11") (pintype "bidirectional"))
      (node (ref "U2") (pin "20") (pinfunction "DVSS_20") (pintype "bidirectional"))
      (node (ref "U2") (pin "24") (pinfunction "DVSS_24") (pintype "bidirectional"))
      (node (ref "U2") (pin "33") (pinfunction "CLKI_33") (pintype "bidirectional"))
      (node (ref "U2") (pin "35") (pinfunction "DVSS_35") (pintype "bidirectional"))
      (node (ref "U2") (pin "45") (pinfunction "DVSS_45") (pintype "bidirectional"))
      (node (ref "U2") (pin "55") (pinfunction "DVSS_55") (pintype "bidirectional"))
      (node (ref "U2") (pin "58") (pinfunction "AVSS_58") (pintype "bidirectional"))
      (node (ref "U2") (pin "61") (pinfunction "AVSS_61") (pintype "bidirectional"))
      (node (ref "U2") (pin "7") (pinfunction "AVSS_RFP_7") (pintype "bidirectional"))
    )
    (net (code "12") (name "MISO") (class "Default")
      (node (ref "J1") (pin "1") (pinfunction "1_1") (pintype "passive"))
      (node (ref "U2") (pin "39") (pinfunction "PB3(MISO/PDO/PCINT3)_39") (pintype "bidirectional"))
    )
    (net (code "13") (name "MOSI") (class "Default")
      (node (ref "J1") (pin "4") (pinfunction "4_4") (pintype "passive"))
      (node (ref "U2") (pin "38") (pinfunction "PB2(MOSI/PDI/PCINT2)_38") (pintype "bidirectional"))
    )
    (net (code "14") (name "Net-(B2-GND-Pad2)") (class "Default")
      (node (ref "B2") (pin "2") (pinfunction "GND_2") (pintype "bidirectional"))
      (node (ref "C22") (pin "2") (pinfunction "2_2") (pintype "passive"))
    )
    (net (code "15") (name "Net-(B2-OUT1)") (class "Default")
      (node (ref "B2") (pin "4") (pinfunction "OUT1_4") (pintype "bidirectional"))
      (node (ref "U2") (pin "8") (pinfunction "RFP_8") (pintype "bidirectional"))
    )
    (net (code "16") (name "Net-(B2-OUT2)") (class "Default")
      (node (ref "B2") (pin "3") (pinfunction "OUT2_3") (pintype "bidirectional"))
      (node (ref "U2") (pin "9") (pinfunction "RFN_9") (pintype "bidirectional"))
    )
    (net (code "17") (name "Net-(BATT1-P)") (class "Default")
      (node (ref "BATT1") (pin "+") (pinfunction "P_+") (pintype "bidirectional"))
      (node (ref "J2") (pin "2") (pinfunction "2_2") (pintype "passive"))
    )
    (net (code "18") (name "Net-(C23-Pad1)") (class "Default")
      (node (ref "C23") (pin "1") (pinfunction "1_1") (pintype "passive"))
      (node (ref "U2") (pin "21") (pinfunction "DVDD_21") (pintype "bidirectional"))
      (node (ref "U2") (pin "22") (pinfunction "DVDD_22") (pintype "bidirectional"))
    )
    (net (code "19") (name "Net-(D5-PadA)") (class "Default")
      (node (ref "D5") (pin "A") (pinfunction "A_A") (pintype "passive"))
      (node (ref "R7") (pin "1") (pinfunction "1_1") (pintype "passive"))
    )
    (net (code "20") (name "Net-(D7-PadA)") (class "Default")
      (node (ref "D7") (pin "A") (pinfunction "A_A") (pintype "passive"))
      (node (ref "R3") (pin "1") (pinfunction "1_1") (pintype "passive"))
    )
    (net (code "21") (name "Net-(D8-PadA)") (class "Default")
      (node (ref "D8") (pin "A") (pinfunction "A_A") (pintype "passive"))
      (node (ref "R4") (pin "1") (pinfunction "1_1") (pintype "passive"))
    )
    (net (code "22") (name "Net-(D9-PadA)") (class "Default")
      (node (ref "D9") (pin "A") (pinfunction "A_A") (pintype "passive"))
      (node (ref "R9") (pin "1") (pinfunction "1_1") (pintype "passive"))
    )
    (net (code "23") (name "Net-(MOSFET1-D)") (class "Default")
      (node (ref "D1") (pin "A") (pinfunction "A_A") (pintype "passive"))
      (node (ref "MOSFET1") (pin "3") (pinfunction "D_3") (pintype "passive"))
      (node (ref "U$1") (pin "V-") (pinfunction "V-_V-") (pintype "bidirectional"))
    )
    (net (code "24") (name "Net-(MOSFET1-G)") (class "Default")
      (node (ref "C13") (pin "1") (pinfunction "1_1") (pintype "passive"))
      (node (ref "MOSFET1") (pin "1") (pinfunction "G_1") (pintype "passive"))
      (node (ref "R11") (pin "2") (pinfunction "2_2") (pintype "passive"))
      (node (ref "R12") (pin "2") (pinfunction "2_2") (pintype "passive"))
    )
    (net (code "25") (name "Net-(MOSFET2-D)") (class "Default")
      (node (ref "D2") (pin "A") (pinfunction "A_A") (pintype "passive"))
      (node (ref "MOSFET2") (pin "3") (pinfunction "D_3") (pintype "passive"))
      (node (ref "U$2") (pin "V-") (pinfunction "V-_V-") (pintype "bidirectional"))
    )
    (net (code "26") (name "Net-(MOSFET2-G)") (class "Default")
      (node (ref "C14") (pin "1") (pinfunction "1_1") (pintype "passive"))
      (node (ref "MOSFET2") (pin "1") (pinfunction "G_1") (pintype "passive"))
      (node (ref "R13") (pin "2") (pinfunction "2_2") (pintype "passive"))
      (node (ref "R14") (pin "2") (pinfunction "2_2") (pintype "passive"))
    )
    (net (code "27") (name "Net-(MOSFET3-D)") (class "Default")
      (node (ref "D3") (pin "A") (pinfunction "A_A") (pintype "passive"))
      (node (ref "MOSFET3") (pin "3") (pinfunction "D_3") (pintype "passive"))
      (node (ref "U$3") (pin "V-") (pinfunction "V-_V-") (pintype "bidirectional"))
    )
    (net (code "28") (name "Net-(MOSFET3-G)") (class "Default")
      (node (ref "C10") (pin "1") (pinfunction "1_1") (pintype "passive"))
      (node (ref "MOSFET3") (pin "1") (pinfunction "G_1") (pintype "passive"))
      (node (ref "R15") (pin "2") (pinfunction "2_2") (pintype "passive"))
      (node (ref "R16") (pin "2") (pinfunction "2_2") (pintype "passive"))
    )
    (net (code "29") (name "Net-(MOSFET4-D)") (class "Default")
      (node (ref "D4") (pin "A") (pinfunction "A_A") (pintype "passive"))
      (node (ref "MOSFET4") (pin "3") (pinfunction "D_3") (pintype "passive"))
      (node (ref "U$4") (pin "V-") (pinfunction "V-_V-") (pintype "bidirectional"))
    )
    (net (code "30") (name "Net-(MOSFET4-G)") (class "Default")
      (node (ref "C6") (pin "1") (pinfunction "1_1") (pintype "passive"))
      (node (ref "MOSFET4") (pin "1") (pinfunction "G_1") (pintype "passive"))
      (node (ref "R17") (pin "2") (pinfunction "2_2") (pintype "passive"))
      (node (ref "R18") (pin "2") (pinfunction "2_2") (pintype "passive"))
    )
    (net (code "31") (name "Net-(RX_LED-PadA)") (class "Default")
      (node (ref "RX_LED") (pin "A") (pinfunction "A_A") (pintype "passive"))
      (node (ref "RX_R") (pin "1") (pinfunction "1_1") (pintype "passive"))
    )
    (net (code "32") (name "Net-(SERIAL_PROGRAMMER-1)") (class "Default")
      (node (ref "C15") (pin "1") (pinfunction "1_1") (pintype "passive"))
      (node (ref "SERIAL_PROGRAMMER") (pin "DTR") (pinfunction "1_DTR") (pintype "passive"))
    )
    (net (code "33") (name "Net-(TX_LED-PadA)") (class "Default")
      (node (ref "TX_LED") (pin "A") (pinfunction "A_A") (pintype "passive"))
      (node (ref "TX_R") (pin "1") (pinfunction "1_1") (pintype "passive"))
    )
    (net (code "34") (name "Net-(U$6-C1)") (class "Default")
      (node (ref "C20") (pin "2") (pinfunction "2_2") (pintype "passive"))
      (node (ref "U$6") (pin "24") (pinfunction "C1_24") (pintype "bidirectional"))
    )
    (net (code "35") (name "Net-(U$6-CAP)") (class "Default")
      (node (ref "C21") (pin "1") (pinfunction "1_1") (pintype "passive"))
      (node (ref "U$6") (pin "21") (pinfunction "CAP_21") (pintype "bidirectional"))
    )
    (net (code "36") (name "Net-(U$9-NC{slash}FB)") (class "Default")
      (node (ref "C12") (pin "1") (pinfunction "1_1") (pintype "passive"))
      (node (ref "U$9") (pin "4") (pinfunction "NC/FB_4") (pintype "passive"))
    )
    (net (code "37") (name "Net-(U2-AVDD)") (class "Default")
      (node (ref "C11") (pin "1") (pinfunction "1_1") (pintype "passive"))
      (node (ref "U2") (pin "60") (pinfunction "AVDD_60") (pintype "bidirectional"))
    )
    (net (code "38") (name "Net-(U2-XTAL1)") (class "Default")
      (node (ref "C2") (pin "1") (pinfunction "1_1") (pintype "passive"))
      (node (ref "U2") (pin "57") (pinfunction "XTAL1_57") (pintype "bidirectional"))
      (node (ref "Y2") (pin "3") (pinfunction "2_3") (pintype "passive"))
    )
    (net (code "39") (name "Net-(U2-XTAL2)") (class "Default")
      (node (ref "C1") (pin "1") (pinfunction "1_1") (pintype "passive"))
      (node (ref "U2") (pin "56") (pinfunction "XTAL2_56") (pintype "bidirectional"))
      (node (ref "Y2") (pin "1") (pinfunction "1_1") (pintype "passive"))
    )
    (net (code "40") (name "PB4") (class "Default")
      (node (ref "U2") (pin "40") (pinfunction "PB4(OC2A/PCINT4)_40") (pintype "bidirectional"))
    )
    (net (code "41") (name "PB6") (class "Default")
      (node (ref "U2") (pin "42") (pinfunction "PB6(OC1B/PCINT6)_42") (pintype "bidirectional"))
    )
    (net (code "42") (name "PB7") (class "Default")
      (node (ref "U2") (pin "43") (pinfunction "PB7(OC0A/OC1C/PCINT7)_43") (pintype "bidirectional"))
    )
    (net (code "43") (name "PD4") (class "Default")
      (node (ref "U2") (pin "29") (pinfunction "PD4(ICP1)_29") (pintype "bidirectional"))
    )
    (net (code "44") (name "PD5") (class "Default")
      (node (ref "U2") (pin "30") (pinfunction "PD5(XCK1)_30") (pintype "bidirectional"))
    )
    (net (code "45") (name "PD6") (class "Default")
      (node (ref "U2") (pin "31") (pinfunction "PD6(T1)_31") (pintype "bidirectional"))
    )
    (net (code "46") (name "PD7") (class "Default")
      (node (ref "U2") (pin "32") (pinfunction "PD7(T0)_32") (pintype "bidirectional"))
    )
    (net (code "47") (name "PE2") (class "Default")
      (node (ref "U2") (pin "48") (pinfunction "PE2(XCK0/AIN0)_48") (pintype "bidirectional"))
    )
    (net (code "48") (name "PE6") (class "Default")
      (node (ref "U2") (pin "52") (pinfunction "PE6(T3/INT6)_52") (pintype "bidirectional"))
    )
    (net (code "49") (name "PE7") (class "Default")
      (node (ref "U2") (pin "53") (pinfunction "PE7(ICP3/INT7/CLKO)_53") (pintype "bidirectional"))
    )
    (net (code "50") (name "PG0") (class "Default")
      (node (ref "U2") (pin "14") (pinfunction "PG0(DIG3)_14") (pintype "bidirectional"))
    )
    (net (code "51") (name "PG1") (class "Default")
      (node (ref "U2") (pin "15") (pinfunction "PG1(DIG1)_15") (pintype "bidirectional"))
    )
    (net (code "52") (name "PG2") (class "Default")
      (node (ref "U2") (pin "16") (pinfunction "PG2(AMR)_16") (pintype "bidirectional"))
    )
    (net (code "53") (name "PWM1") (class "Default")
      (node (ref "BREAKOUT_HEADER") (pin "6") (pinfunction "6_6") (pintype "passive"))
      (node (ref "M1") (pin "2") (pinfunction "2_2") (pintype "passive"))
      (node (ref "R12") (pin "1") (pinfunction "1_1") (pintype "passive"))
      (node (ref "U2") (pin "41") (pinfunction "PB5(OC1A/PCINT5)_41") (pintype "bidirectional"))
    )
    (net (code "54") (name "PWM2") (class "Default")
      (node (ref "BREAKOUT_HEADER") (pin "5") (pinfunction "5_5") (pintype "passive"))
      (node (ref "M2") (pin "2") (pinfunction "2_2") (pintype "passive"))
      (node (ref "R14") (pin "1") (pinfunction "1_1") (pintype "passive"))
      (node (ref "U2") (pin "51") (pinfunction "PE5(OC3C/INT5)_51") (pintype "bidirectional"))
    )
    (net (code "55") (name "PWM3") (class "Default")
      (node (ref "BREAKOUT_HEADER") (pin "4") (pinfunction "4_4") (pintype "passive"))
      (node (ref "M3") (pin "2") (pinfunction "2_2") (pintype "passive"))
      (node (ref "R16") (pin "1") (pinfunction "1_1") (pintype "passive"))
      (node (ref "U2") (pin "49") (pinfunction "PE3(OC3A/AIN1)_49") (pintype "bidirectional"))
    )
    (net (code "56") (name "PWM4") (class "Default")
      (node (ref "BREAKOUT_HEADER") (pin "3") (pinfunction "3_3") (pintype "passive"))
      (node (ref "M4") (pin "2") (pinfunction "2_2") (pintype "passive"))
      (node (ref "R18") (pin "1") (pinfunction "1_1") (pintype "passive"))
      (node (ref "U2") (pin "50") (pinfunction "PE4(OC3B/INT4)_50") (pintype "bidirectional"))
    )
    (net (code "57") (name "RESET") (class "Default")
      (node (ref "C15") (pin "2") (pinfunction "2_2") (pintype "passive"))
      (node (ref "J1") (pin "5") (pinfunction "5_5") (pintype "passive"))
      (node (ref "R1") (pin "1") (pinfunction "1_1") (pintype "passive"))
      (node (ref "SWRESET") (pin "3") (pinfunction "2_3") (pintype "passive"))
      (node (ref "SWRESET") (pin "4") (pinfunction "2_4") (pintype "passive"))
      (node (ref "U2") (pin "12") (pinfunction "RSTN_12") (pintype "bidirectional"))
    )
    (net (code "58") (name "RSTON") (class "Default")
      (node (ref "U2") (pin "13") (pinfunction "RSTON_13") (pintype "bidirectional"))
    )
    (net (code "59") (name "RX0") (class "Default")
      (node (ref "RX_R") (pin "2") (pinfunction "2_2") (pintype "passive"))
      (node (ref "SERIAL_PROGRAMMER") (pin "TXO") (pinfunction "3_TXO") (pintype "passive"))
      (node (ref "U2") (pin "46") (pinfunction "PE0(RXD0/PCINT8)_46") (pintype "bidirectional"))
    )
    (net (code "60") (name "RX1") (class "Default")
      (node (ref "SERIAL_DEBUGGER") (pin "TXO") (pinfunction "3_TXO") (pintype "passive"))
      (node (ref "U2") (pin "27") (pinfunction "PD2(RXD1/INT2)_27") (pintype "bidirectional"))
    )
    (net (code "61") (name "SCK") (class "Default")
      (node (ref "J1") (pin "3") (pinfunction "3_3") (pintype "passive"))
      (node (ref "U2") (pin "37") (pinfunction "PB1(SCK/PCINT1)_37") (pintype "bidirectional"))
    )
    (net (code "62") (name "SCL") (class "Default")
      (node (ref "BREAKOUT_HEADER") (pin "1") (pinfunction "1_1") (pintype "passive"))
      (node (ref "R8") (pin "1") (pinfunction "1_1") (pintype "passive"))
      (node (ref "U$6") (pin "2") (pinfunction "SCL/SPC_2") (pintype "bidirectional"))
      (node (ref "U2") (pin "25") (pinfunction "PD0(SCL/INT0)_25") (pintype "bidirectional"))
    )
    (net (code "63") (name "SDA") (class "Default")
      (node (ref "BREAKOUT_HEADER") (pin "2") (pinfunction "2_2") (pintype "passive"))
      (node (ref "R2") (pin "1") (pinfunction "1_1") (pintype "passive"))
      (node (ref "U$6") (pin "4") (pinfunction "SDA/SDI/SDO_4") (pintype "bidirectional"))
      (node (ref "U2") (pin "26") (pinfunction "PD1(SDA/INT1)_26") (pintype "bidirectional"))
    )
    (net (code "64") (name "SSN") (class "Default")
      (node (ref "U2") (pin "36") (pinfunction "PB0(SSN/PCINT0)_36") (pintype "bidirectional"))
    )
    (net (code "65") (name "TX0") (class "Default")
      (node (ref "SERIAL_PROGRAMMER") (pin "RXI") (pinfunction "2_RXI") (pintype "passive"))
      (node (ref "TX_R") (pin "2") (pinfunction "2_2") (pintype "passive"))
      (node (ref "U2") (pin "47") (pinfunction "PE1(TXD0)_47") (pintype "bidirectional"))
    )
    (net (code "66") (name "TX1") (class "Default")
      (node (ref "SERIAL_DEBUGGER") (pin "RXI") (pinfunction "2_RXI") (pintype "passive"))
      (node (ref "U2") (pin "28") (pinfunction "PD3(TXD1/INT3)_28") (pintype "bidirectional"))
    )
    (net (code "67") (name "VBAT") (class "Default")
      (node (ref "BREAKOUT_HEADER") (pin "8") (pinfunction "8_8") (pintype "passive"))
      (node (ref "C18") (pin "1") (pinfunction "1_1") (pintype "passive"))
      (node (ref "C24") (pin "1") (pinfunction "+_1") (pintype "passive"))
      (node (ref "C25") (pin "1") (pinfunction "+_1") (pintype "passive"))
      (node (ref "C5") (pin "1") (pinfunction "+_1") (pintype "passive"))
      (node (ref "C7") (pin "1") (pinfunction "+_1") (pintype "passive"))
      (node (ref "C8") (pin "1") (pinfunction "+_1") (pintype "passive"))
      (node (ref "D1") (pin "C") (pinfunction "C_C") (pintype "passive"))
      (node (ref "D2") (pin "C") (pinfunction "C_C") (pintype "passive"))
      (node (ref "D3") (pin "C") (pinfunction "C_C") (pintype "passive"))
      (node (ref "D4") (pin "C") (pinfunction "C_C") (pintype "passive"))
      (node (ref "J2") (pin "1") (pinfunction "1_1") (pintype "passive"))
      (node (ref "R3") (pin "2") (pinfunction "2_2") (pintype "passive"))
      (node (ref "R4") (pin "2") (pinfunction "2_2") (pintype "passive"))
      (node (ref "R5") (pin "2") (pinfunction "2_2") (pintype "passive"))
      (node (ref "R9") (pin "2") (pinfunction "2_2") (pintype "passive"))
      (node (ref "U$1") (pin "V+") (pinfunction "V+_V+") (pintype "bidirectional"))
      (node (ref "U$2") (pin "V+") (pinfunction "V+_V+") (pintype "bidirectional"))
      (node (ref "U$3") (pin "V+") (pinfunction "V+_V+") (pintype "bidirectional"))
      (node (ref "U$4") (pin "V+") (pinfunction "V+_V+") (pintype "bidirectional"))
      (node (ref "U$9") (pin "1") (pinfunction "IN_1") (pintype "input"))
      (node (ref "U$9") (pin "3") (pinfunction "EN_3") (pintype "input"))
    )
    (net (code "68") (name "VBAT_SENSE") (class "Default")
      (node (ref "R5") (pin "1") (pinfunction "1_1") (pintype "passive"))
      (node (ref "R6") (pin "2") (pinfunction "2_2") (pintype "passive"))
      (node (ref "U2") (pin "63") (pinfunction "PF0(ADC0)_63") (pintype "bidirectional"))
    )
    (net (code "69") (name "unconnected-(J1-Pad2)") (class "Default")
      (node (ref "J1") (pin "2") (pinfunction "2_2") (pintype "passive"))
    )
    (net (code "70") (name "unconnected-(SERIAL_DEBUGGER-1-PadDTR)") (class "Default")
      (node (ref "SERIAL_DEBUGGER") (pin "DTR") (pinfunction "1_DTR") (pintype "passive"))
    )
    (net (code "71") (name "unconnected-(SERIAL_DEBUGGER-4-PadVCC)") (class "Default")
      (node (ref "SERIAL_DEBUGGER") (pin "VCC") (pinfunction "4_VCC") (pintype "passive"))
    )
    (net (code "72") (name "unconnected-(SERIAL_DEBUGGER-5-PadCTS)") (class "Default")
      (node (ref "SERIAL_DEBUGGER") (pin "CTS") (pinfunction "5_CTS") (pintype "passive"))
    )
    (net (code "73") (name "unconnected-(SERIAL_PROGRAMMER-4-PadVCC)") (class "Default")
      (node (ref "SERIAL_PROGRAMMER") (pin "VCC") (pinfunction "4_VCC") (pintype "passive"))
    )
    (net (code "74") (name "unconnected-(SERIAL_PROGRAMMER-5-PadCTS)") (class "Default")
      (node (ref "SERIAL_PROGRAMMER") (pin "CTS") (pinfunction "5_CTS") (pintype "passive"))
    )
    (net (code "75") (name "unconnected-(U$6-DRDY_M-Pad9)") (class "Default")
      (node (ref "U$6") (pin "9") (pinfunction "DRDY_M_9") (pintype "bidirectional"))
    )
    (net (code "76") (name "unconnected-(U$6-INT1_A{slash}G-Pad11)") (class "Default")
      (node (ref "U$6") (pin "11") (pinfunction "INT1_A/G_11") (pintype "bidirectional"))
    )
    (net (code "77") (name "unconnected-(U$6-INT2_A{slash}G-Pad12)") (class "Default")
      (node (ref "U$6") (pin "12") (pinfunction "INT2_A/G_12") (pintype "bidirectional"))
    )
    (net (code "78") (name "unconnected-(U$6-INT_M-Pad10)") (class "Default")
      (node (ref "U$6") (pin "10") (pinfunction "INT_M_10") (pintype "bidirectional"))
    )
    (net (code "79") (name "unconnected-(U2-PADDLE-Pad65)") (class "Default")
      (node (ref "U2") (pin "65") (pinfunction "PADDLE_65") (pintype "bidirectional"))
    )
    (net (code "80") (name "unconnected-(U2-PG3(TOSC2)-Pad17)") (class "Default")
      (node (ref "U2") (pin "17") (pinfunction "PG3(TOSC2)_17") (pintype "bidirectional"))
    )
    (net (code "81") (name "unconnected-(U2-PG4(TOSC1)-Pad18)") (class "Default")
      (node (ref "U2") (pin "18") (pinfunction "PG4(TOSC1)_18") (pintype "bidirectional"))
    )
    (net (code "82") (name "unconnected-(U2-PG5(OC0B)-Pad19)") (class "Default")
      (node (ref "U2") (pin "19") (pinfunction "PG5(OC0B)_19") (pintype "bidirectional"))
    )
  )
)
